# 5V_Boost_Converter.net
KiCad netlist of a schematic drawn in EAGLE
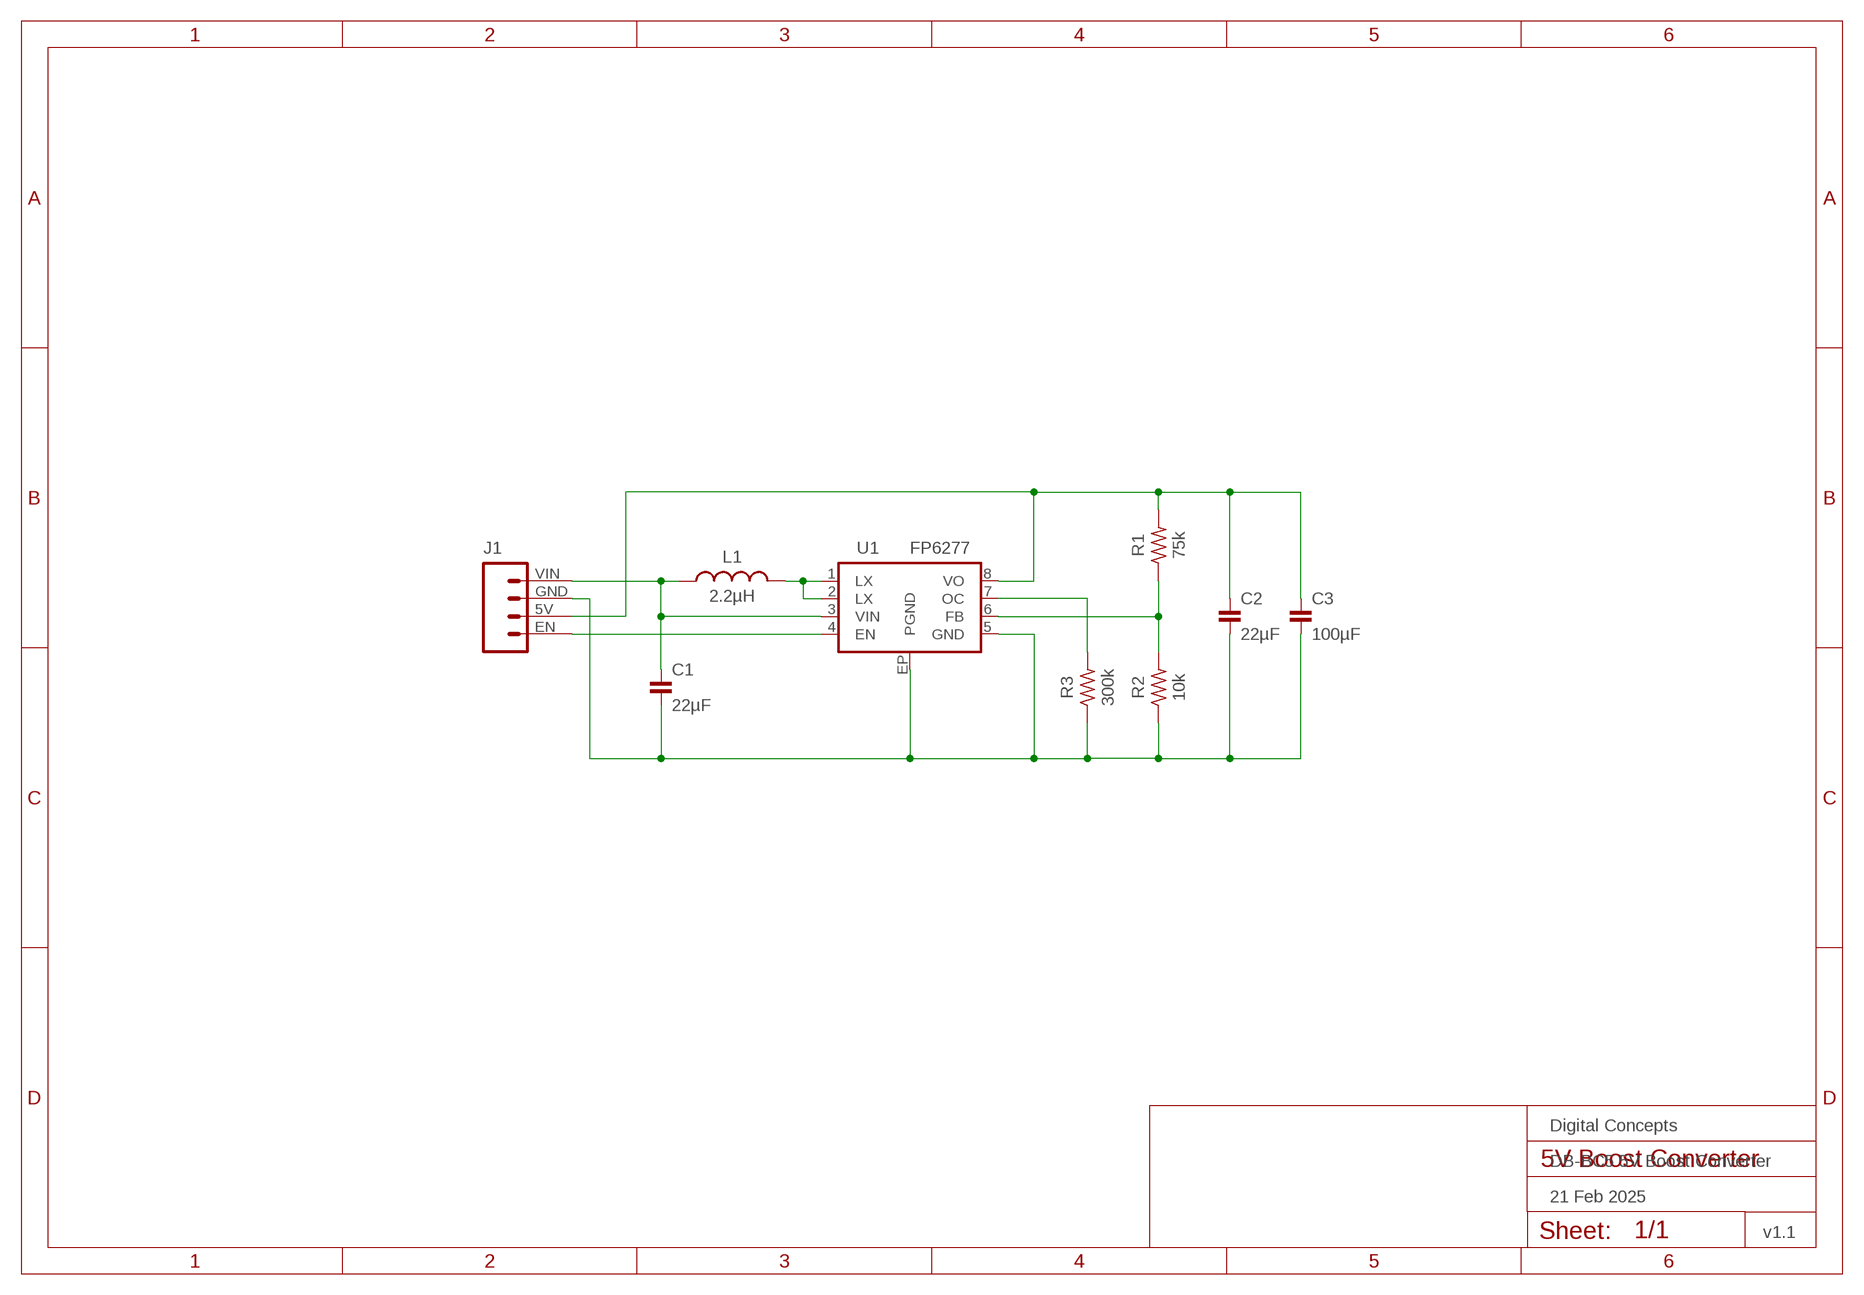
[diagram p0: schematic, sheet 1]

(export (version "E")
  (design (tool "Eeschema 10.0.6"))
  (components
    (comp (ref "C1")
      (value "22µF")
      (footprint "eagle-import:C0805")
      (libsource (lib "eagle-import") (part "CAPACITOR-0805"))
    )
    (comp (ref "C2")
      (value "22µF")
      (footprint "eagle-import:C0805")
      (libsource (lib "eagle-import") (part "CAPACITOR-0805"))
    )
    (comp (ref "C3")
      (value "100µF")
      (footprint "eagle-import:C1206")
      (libsource (lib "eagle-import") (part "CAPACITOR-1206"))
    )
    (comp (ref "J1")
      (value "HEADER-1X4-FP6277")
      (footprint "eagle-import:CONN_04-FP6277")
      (libsource (lib "eagle-import") (part "HEADER-1X4-FP6277"))
    )
    (comp (ref "L1")
      (value "2.2µH")
      (footprint "eagle-import:L1008")
      (libsource (lib "eagle-import") (part "INDUCTOR-LQM2HPN2R2MG0L"))
    )
    (comp (ref "R1")
      (value "75k")
      (footprint "eagle-import:R0805")
      (libsource (lib "eagle-import") (part "RESISTORR0805"))
    )
    (comp (ref "R2")
      (value "10k")
      (footprint "eagle-import:R0805")
      (libsource (lib "eagle-import") (part "RESISTORR0805"))
    )
    (comp (ref "R3")
      (value "300k")
      (footprint "eagle-import:R0805")
      (libsource (lib "eagle-import") (part "RESISTORR0805"))
    )
    (comp (ref "U1")
      (value "FP6277")
      (footprint "eagle-import:SOP-8(EP)")
      (libsource (lib "eagle-import") (part "FP6277"))
    )
  )
  (nets
    (net (code "1") (name "Net-(J1-1)") (class "Default")
      (node (ref "J1") (pin "EN") (pinfunction "1_EN") (pintype "passive"))
      (node (ref "U1") (pin "4") (pinfunction "EN_4") (pintype "input"))
    )
    (net (code "2") (name "Net-(J1-2)") (class "Default")
      (node (ref "C2") (pin "1") (pinfunction "1_1") (pintype "passive"))
      (node (ref "C3") (pin "1") (pinfunction "1_1") (pintype "passive"))
      (node (ref "J1") (pin "5V") (pinfunction "2_5V") (pintype "passive"))
      (node (ref "R1") (pin "2") (pinfunction "2_2") (pintype "passive"))
      (node (ref "U1") (pin "8") (pinfunction "VO_8") (pintype "power_in"))
    )
    (net (code "3") (name "Net-(J1-3)") (class "Default")
      (node (ref "C1") (pin "2") (pinfunction "2_2") (pintype "passive"))
      (node (ref "C2") (pin "2") (pinfunction "2_2") (pintype "passive"))
      (node (ref "C3") (pin "2") (pinfunction "2_2") (pintype "passive"))
      (node (ref "J1") (pin "GND") (pinfunction "3_GND") (pintype "passive"))
      (node (ref "R2") (pin "1") (pinfunction "1_1") (pintype "passive"))
      (node (ref "R3") (pin "1") (pinfunction "1_1") (pintype "passive"))
      (node (ref "U1") (pin "5") (pinfunction "GND_5") (pintype "power_in"))
      (node (ref "U1") (pin "EP") (pinfunction "PGND_EP") (pintype "power_in"))
    )
    (net (code "4") (name "Net-(J1-4)") (class "Default")
      (node (ref "C1") (pin "1") (pinfunction "1_1") (pintype "passive"))
      (node (ref "J1") (pin "VIN") (pinfunction "4_VIN") (pintype "passive"))
      (node (ref "L1") (pin "P$2") (pinfunction "2_P$2") (pintype "passive"))
      (node (ref "U1") (pin "3") (pinfunction "VIN_3") (pintype "power_in"))
    )
    (net (code "5") (name "Net-(L1-1)") (class "Default")
      (node (ref "L1") (pin "P$1") (pinfunction "1_P$1") (pintype "passive"))
      (node (ref "U1") (pin "1") (pinfunction "LX_1") (pintype "input"))
      (node (ref "U1") (pin "2") (pinfunction "LX_2") (pintype "input"))
    )
    (net (code "6") (name "Net-(U1-FB)") (class "Default")
      (node (ref "R1") (pin "1") (pinfunction "1_1") (pintype "passive"))
      (node (ref "R2") (pin "2") (pinfunction "2_2") (pintype "passive"))
      (node (ref "U1") (pin "6") (pinfunction "FB_6") (pintype "input"))
    )
    (net (code "7") (name "Net-(U1-OC)") (class "Default")
      (node (ref "R3") (pin "2") (pinfunction "2_2") (pintype "passive"))
      (node (ref "U1") (pin "7") (pinfunction "OC_7") (pintype "input"))
    )
  )
)
